# Samid6322.net
KiCad netlist of a schematic drawn in EAGLE
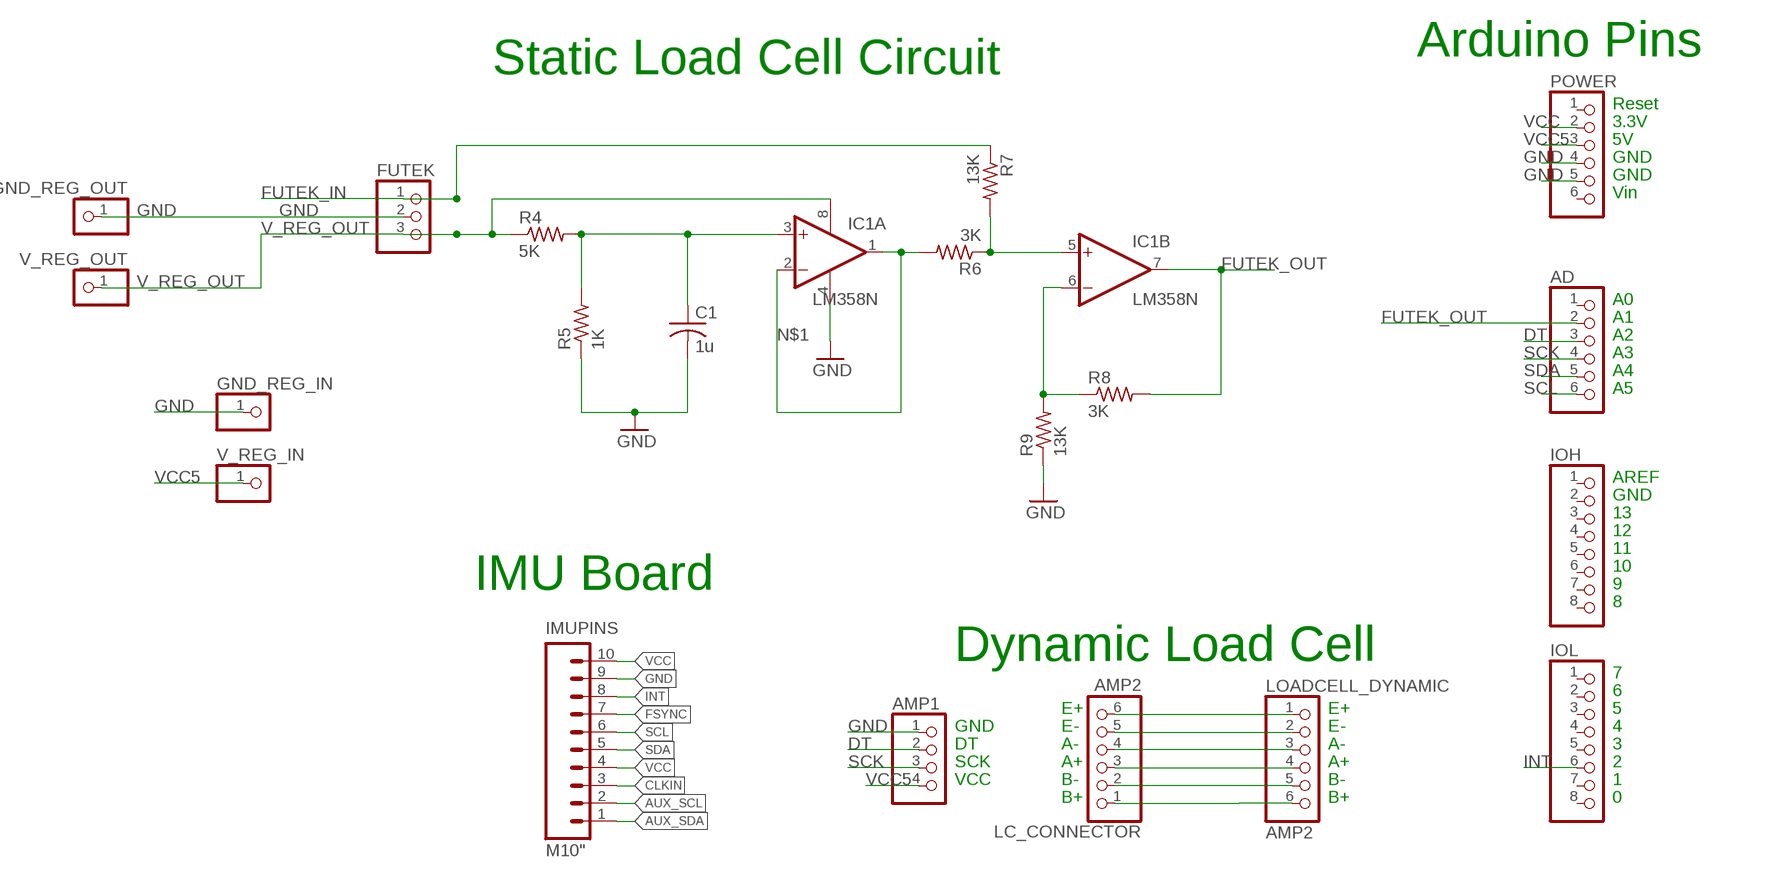
[diagram p0: schematic, sheet 1]

(export (version "E")
  (design (tool "Eeschema 10.0.6"))
  (components
    (comp (ref "AD")
      (value "PINHD-1X6")
      (footprint "eagle-import:1X06")
      (libsource (lib "eagle-import") (part "PINHD-1X6"))
    )
    (comp (ref "AMP1")
      (value "PINHD-1X4")
      (footprint "eagle-import:1X04")
      (libsource (lib "eagle-import") (part "PINHD-1X4"))
    )
    (comp (ref "C1")
      (value "1u")
      (footprint "eagle-import:C025-024X044")
      (libsource (lib "eagle-import") (part "C-US025-024X044"))
    )
    (comp (ref "FUTEK")
      (value "PINHD-1X3")
      (footprint "eagle-import:1X03")
      (libsource (lib "eagle-import") (part "PINHD-1X3"))
    )
    (comp (ref "GND_REG_IN")
      (value "PINHD-1X1")
      (footprint "eagle-import:1X01")
      (libsource (lib "eagle-import") (part "PINHD-1X1"))
    )
    (comp (ref "GND_REG_OUT")
      (value "PINHD-1X1")
      (footprint "eagle-import:1X01")
      (libsource (lib "eagle-import") (part "PINHD-1X1"))
    )
    (comp (ref "IC1")
      (value "LM358N")
      (footprint "eagle-import:DIL08")
      (libsource (lib "eagle-import") (part "LM358N"))
    )
    (comp (ref "IMUPINS")
      (value "M10\"")
      (footprint "eagle-import:1X10")
      (libsource (lib "eagle-import") (part "M10{dblquote}"))
    )
    (comp (ref "IOH")
      (value "PINHD-1X8")
      (footprint "eagle-import:1X08")
      (libsource (lib "eagle-import") (part "PINHD-1X8"))
    )
    (comp (ref "IOL")
      (value "PINHD-1X8")
      (footprint "eagle-import:1X08")
      (libsource (lib "eagle-import") (part "PINHD-1X8"))
    )
    (comp (ref "LC_CONNECTOR")
      (value "AMP2")
      (footprint "eagle-import:1X06")
      (libsource (lib "eagle-import") (part "PINHD-1X6"))
    )
    (comp (ref "LOADCELL_DYNAMIC")
      (value "AMP2")
      (footprint "eagle-import:1X06")
      (libsource (lib "eagle-import") (part "PINHD-1X6"))
    )
    (comp (ref "POWER")
      (value "PINHD-1X6")
      (footprint "eagle-import:1X06")
      (libsource (lib "eagle-import") (part "PINHD-1X6"))
    )
    (comp (ref "R4")
      (value "5K")
      (footprint "eagle-import:0204_7")
      (libsource (lib "eagle-import") (part "R-US_0204/7"))
    )
    (comp (ref "R5")
      (value "1K")
      (footprint "eagle-import:0204_7")
      (libsource (lib "eagle-import") (part "R-US_0204/7"))
    )
    (comp (ref "R6")
      (value "3K")
      (footprint "eagle-import:0204_7")
      (libsource (lib "eagle-import") (part "R-US_0204/7"))
    )
    (comp (ref "R7")
      (value "13K")
      (footprint "eagle-import:0204_7")
      (libsource (lib "eagle-import") (part "R-US_0204/7"))
    )
    (comp (ref "R8")
      (value "3K")
      (footprint "eagle-import:0204_7")
      (libsource (lib "eagle-import") (part "R-US_0204/7"))
    )
    (comp (ref "R9")
      (value "13K")
      (footprint "eagle-import:0204_7")
      (libsource (lib "eagle-import") (part "R-US_0204/7"))
    )
    (comp (ref "V_REG_IN")
      (value "PINHD-1X1")
      (footprint "eagle-import:1X01")
      (libsource (lib "eagle-import") (part "PINHD-1X1"))
    )
    (comp (ref "V_REG_OUT")
      (value "PINHD-1X1")
      (footprint "eagle-import:1X01")
      (libsource (lib "eagle-import") (part "PINHD-1X1"))
    )
  )
  (nets
    (net (code "1") (name "/DT") (class "Default")
      (node (ref "AD") (pin "3") (pinfunction "3_3") (pintype "passive"))
      (node (ref "AMP1") (pin "2") (pinfunction "2_2") (pintype "passive"))
    )
    (net (code "2") (name "/FUTEK_IN") (class "Default")
      (node (ref "FUTEK") (pin "1") (pinfunction "1_1") (pintype "passive"))
      (node (ref "R7") (pin "1") (pinfunction "1_1") (pintype "passive"))
    )
    (net (code "3") (name "/FUTEK_OUT") (class "Default")
      (node (ref "AD") (pin "2") (pinfunction "2_2") (pintype "passive"))
      (node (ref "IC1") (pin "7") (pinfunction "OUT_7") (pintype "output"))
      (node (ref "R8") (pin "2") (pinfunction "2_2") (pintype "passive"))
    )
    (net (code "4") (name "/N$1") (class "Default")
      (node (ref "IC1") (pin "1") (pinfunction "OUT_1") (pintype "output"))
      (node (ref "IC1") (pin "2") (pinfunction "-IN_2") (pintype "input"))
      (node (ref "R6") (pin "2") (pinfunction "2_2") (pintype "passive"))
    )
    (net (code "5") (name "/SCK") (class "Default")
      (node (ref "AD") (pin "4") (pinfunction "4_4") (pintype "passive"))
      (node (ref "AMP1") (pin "3") (pinfunction "3_3") (pintype "passive"))
    )
    (net (code "6") (name "/VCC5") (class "Default")
      (node (ref "AMP1") (pin "4") (pinfunction "4_4") (pintype "passive"))
      (node (ref "POWER") (pin "3") (pinfunction "3_3") (pintype "passive"))
      (node (ref "V_REG_IN") (pin "1") (pinfunction "1_1") (pintype "passive"))
    )
    (net (code "7") (name "/V_REG_OUT") (class "Default")
      (node (ref "FUTEK") (pin "3") (pinfunction "3_3") (pintype "passive"))
      (node (ref "IC1") (pin "8") (pinfunction "V+_8") (pintype "power_in"))
      (node (ref "R4") (pin "1") (pinfunction "1_1") (pintype "passive"))
      (node (ref "V_REG_OUT") (pin "1") (pinfunction "1_1") (pintype "passive"))
    )
    (net (code "8") (name "AUX_SCL") (class "Default")
      (node (ref "IMUPINS") (pin "2") (pinfunction "2_2") (pintype "passive"))
    )
    (net (code "9") (name "AUX_SDA") (class "Default")
      (node (ref "IMUPINS") (pin "1") (pinfunction "1_1") (pintype "passive"))
    )
    (net (code "10") (name "CLKIN") (class "Default")
      (node (ref "IMUPINS") (pin "3") (pinfunction "3_3") (pintype "passive"))
    )
    (net (code "11") (name "FSYNC") (class "Default")
      (node (ref "IMUPINS") (pin "7") (pinfunction "7_7") (pintype "passive"))
    )
    (net (code "12") (name "GND") (class "Default")
      (node (ref "AMP1") (pin "1") (pinfunction "1_1") (pintype "passive"))
      (node (ref "C1") (pin "2") (pinfunction "2_2") (pintype "passive"))
      (node (ref "FUTEK") (pin "2") (pinfunction "2_2") (pintype "passive"))
      (node (ref "GND_REG_IN") (pin "1") (pinfunction "1_1") (pintype "passive"))
      (node (ref "GND_REG_OUT") (pin "1") (pinfunction "1_1") (pintype "passive"))
      (node (ref "IC1") (pin "4") (pinfunction "V-_4") (pintype "power_in"))
      (node (ref "IMUPINS") (pin "9") (pinfunction "9_9") (pintype "passive"))
      (node (ref "POWER") (pin "4") (pinfunction "4_4") (pintype "passive"))
      (node (ref "POWER") (pin "5") (pinfunction "5_5") (pintype "passive"))
      (node (ref "R5") (pin "1") (pinfunction "1_1") (pintype "passive"))
      (node (ref "R9") (pin "1") (pinfunction "1_1") (pintype "passive"))
    )
    (net (code "13") (name "INT") (class "Default")
      (node (ref "IMUPINS") (pin "8") (pinfunction "8_8") (pintype "passive"))
      (node (ref "IOL") (pin "6") (pinfunction "6_6") (pintype "passive"))
    )
    (net (code "14") (name "Net-(IC1A-+IN)") (class "Default")
      (node (ref "C1") (pin "1") (pinfunction "1_1") (pintype "passive"))
      (node (ref "IC1") (pin "3") (pinfunction "+IN_3") (pintype "input"))
      (node (ref "R4") (pin "2") (pinfunction "2_2") (pintype "passive"))
      (node (ref "R5") (pin "2") (pinfunction "2_2") (pintype "passive"))
    )
    (net (code "15") (name "Net-(IC1B-+IN)") (class "Default")
      (node (ref "IC1") (pin "5") (pinfunction "+IN_5") (pintype "input"))
      (node (ref "R6") (pin "1") (pinfunction "1_1") (pintype "passive"))
      (node (ref "R7") (pin "2") (pinfunction "2_2") (pintype "passive"))
    )
    (net (code "16") (name "Net-(IC1B--IN)") (class "Default")
      (node (ref "IC1") (pin "6") (pinfunction "-IN_6") (pintype "input"))
      (node (ref "R8") (pin "1") (pinfunction "1_1") (pintype "passive"))
      (node (ref "R9") (pin "2") (pinfunction "2_2") (pintype "passive"))
    )
    (net (code "17") (name "Net-(LC_CONNECTOR-Pad1)") (class "Default")
      (node (ref "LC_CONNECTOR") (pin "1") (pinfunction "1_1") (pintype "passive"))
      (node (ref "LOADCELL_DYNAMIC") (pin "6") (pinfunction "6_6") (pintype "passive"))
    )
    (net (code "18") (name "Net-(LC_CONNECTOR-Pad2)") (class "Default")
      (node (ref "LC_CONNECTOR") (pin "2") (pinfunction "2_2") (pintype "passive"))
      (node (ref "LOADCELL_DYNAMIC") (pin "5") (pinfunction "5_5") (pintype "passive"))
    )
    (net (code "19") (name "Net-(LC_CONNECTOR-Pad3)") (class "Default")
      (node (ref "LC_CONNECTOR") (pin "3") (pinfunction "3_3") (pintype "passive"))
      (node (ref "LOADCELL_DYNAMIC") (pin "4") (pinfunction "4_4") (pintype "passive"))
    )
    (net (code "20") (name "Net-(LC_CONNECTOR-Pad4)") (class "Default")
      (node (ref "LC_CONNECTOR") (pin "4") (pinfunction "4_4") (pintype "passive"))
      (node (ref "LOADCELL_DYNAMIC") (pin "3") (pinfunction "3_3") (pintype "passive"))
    )
    (net (code "21") (name "Net-(LC_CONNECTOR-Pad5)") (class "Default")
      (node (ref "LC_CONNECTOR") (pin "5") (pinfunction "5_5") (pintype "passive"))
      (node (ref "LOADCELL_DYNAMIC") (pin "2") (pinfunction "2_2") (pintype "passive"))
    )
    (net (code "22") (name "Net-(LC_CONNECTOR-Pad6)") (class "Default")
      (node (ref "LC_CONNECTOR") (pin "6") (pinfunction "6_6") (pintype "passive"))
      (node (ref "LOADCELL_DYNAMIC") (pin "1") (pinfunction "1_1") (pintype "passive"))
    )
    (net (code "23") (name "SCL") (class "Default")
      (node (ref "AD") (pin "6") (pinfunction "6_6") (pintype "passive"))
      (node (ref "IMUPINS") (pin "6") (pinfunction "6_6") (pintype "passive"))
    )
    (net (code "24") (name "SDA") (class "Default")
      (node (ref "AD") (pin "5") (pinfunction "5_5") (pintype "passive"))
      (node (ref "IMUPINS") (pin "5") (pinfunction "5_5") (pintype "passive"))
    )
    (net (code "25") (name "VCC") (class "Default")
      (node (ref "IMUPINS") (pin "10") (pinfunction "10_10") (pintype "passive"))
      (node (ref "IMUPINS") (pin "4") (pinfunction "4_4") (pintype "passive"))
      (node (ref "POWER") (pin "2") (pinfunction "2_2") (pintype "passive"))
    )
    (net (code "26") (name "unconnected-(AD-Pad1)") (class "Default")
      (node (ref "AD") (pin "1") (pinfunction "1_1") (pintype "passive"))
    )
    (net (code "27") (name "unconnected-(IOH-Pad1)") (class "Default")
      (node (ref "IOH") (pin "1") (pinfunction "1_1") (pintype "passive"))
    )
    (net (code "28") (name "unconnected-(IOH-Pad2)") (class "Default")
      (node (ref "IOH") (pin "2") (pinfunction "2_2") (pintype "passive"))
    )
    (net (code "29") (name "unconnected-(IOH-Pad3)") (class "Default")
      (node (ref "IOH") (pin "3") (pinfunction "3_3") (pintype "passive"))
    )
    (net (code "30") (name "unconnected-(IOH-Pad4)") (class "Default")
      (node (ref "IOH") (pin "4") (pinfunction "4_4") (pintype "passive"))
    )
    (net (code "31") (name "unconnected-(IOH-Pad5)") (class "Default")
      (node (ref "IOH") (pin "5") (pinfunction "5_5") (pintype "passive"))
    )
    (net (code "32") (name "unconnected-(IOH-Pad6)") (class "Default")
      (node (ref "IOH") (pin "6") (pinfunction "6_6") (pintype "passive"))
    )
    (net (code "33") (name "unconnected-(IOH-Pad7)") (class "Default")
      (node (ref "IOH") (pin "7") (pinfunction "7_7") (pintype "passive"))
    )
    (net (code "34") (name "unconnected-(IOH-Pad8)") (class "Default")
      (node (ref "IOH") (pin "8") (pinfunction "8_8") (pintype "passive"))
    )
    (net (code "35") (name "unconnected-(IOL-Pad1)") (class "Default")
      (node (ref "IOL") (pin "1") (pinfunction "1_1") (pintype "passive"))
    )
    (net (code "36") (name "unconnected-(IOL-Pad2)") (class "Default")
      (node (ref "IOL") (pin "2") (pinfunction "2_2") (pintype "passive"))
    )
    (net (code "37") (name "unconnected-(IOL-Pad3)") (class "Default")
      (node (ref "IOL") (pin "3") (pinfunction "3_3") (pintype "passive"))
    )
    (net (code "38") (name "unconnected-(IOL-Pad4)") (class "Default")
      (node (ref "IOL") (pin "4") (pinfunction "4_4") (pintype "passive"))
    )
    (net (code "39") (name "unconnected-(IOL-Pad5)") (class "Default")
      (node (ref "IOL") (pin "5") (pinfunction "5_5") (pintype "passive"))
    )
    (net (code "40") (name "unconnected-(IOL-Pad7)") (class "Default")
      (node (ref "IOL") (pin "7") (pinfunction "7_7") (pintype "passive"))
    )
    (net (code "41") (name "unconnected-(IOL-Pad8)") (class "Default")
      (node (ref "IOL") (pin "8") (pinfunction "8_8") (pintype "passive"))
    )
    (net (code "42") (name "unconnected-(POWER-Pad1)") (class "Default")
      (node (ref "POWER") (pin "1") (pinfunction "1_1") (pintype "passive"))
    )
    (net (code "43") (name "unconnected-(POWER-Pad6)") (class "Default")
      (node (ref "POWER") (pin "6") (pinfunction "6_6") (pintype "passive"))
    )
  )
)
